# LINE_PREAMP.net
KiCad netlist of a schematic drawn in Altium Designer
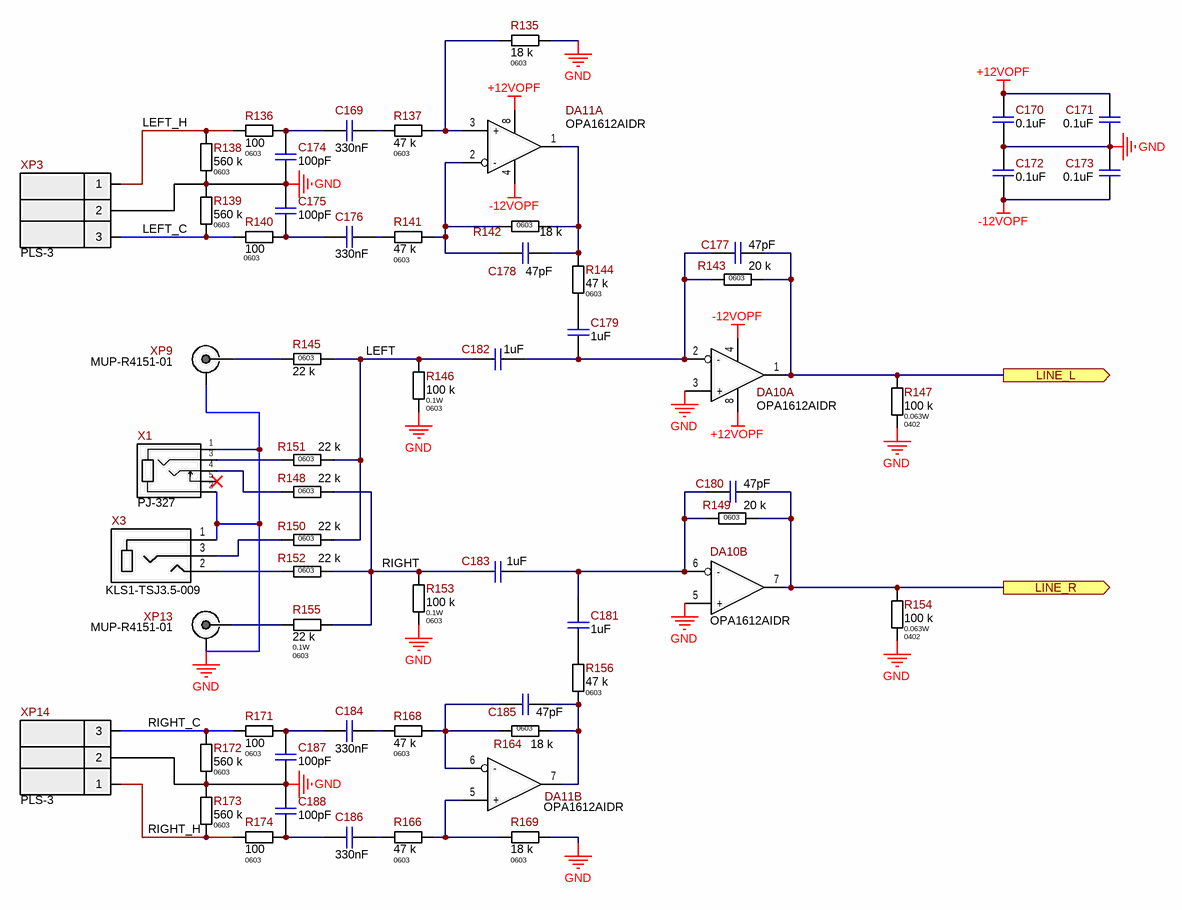
[diagram p0: LINE_PREAMP.SchDoc]

(export (version "E")
  (design (tool "Eeschema 10.0.6"))
  (components
    (comp (ref "C169")
      (value "330nF")
      (footprint "WIMA_2,5x6,5x7,2")
      (description "WIMA 330NF, 40VAC, 63VDC: 5mm, ± 10%")
      (fields (field (name "PART NUMBER") "330nF  AC40V DC63V 2,5x6,5x7,2") (field (name "TOLERANCE") "10%"))
      (libsource (lib "Database") (part "Capacitor_Ceramic"))
    )
    (comp (ref "C170")
      (value "0.1uF")
      (footprint "C0402(1005)")
      (description "CAP CER 0.1UF 25V X7R 0603")
      (fields (field (name "PART NUMBER") "0.1uF  25V C0402") (field (name "TOLERANCE") "±10%"))
      (libsource (lib "Database") (part "Capacitor_Ceramic"))
    )
    (comp (ref "C171")
      (value "0.1uF")
      (footprint "C0402(1005)")
      (description "CAP CER 0.1UF 25V X7R 0603")
      (fields (field (name "PART NUMBER") "0.1uF  25V C0402") (field (name "TOLERANCE") "±10%"))
      (libsource (lib "Database") (part "Capacitor_Ceramic"))
    )
    (comp (ref "C172")
      (value "0.1uF")
      (footprint "C0402(1005)")
      (description "CAP CER 0.1UF 25V X7R 0603")
      (fields (field (name "PART NUMBER") "0.1uF  25V C0402") (field (name "TOLERANCE") "±10%"))
      (libsource (lib "Database") (part "Capacitor_Ceramic"))
    )
    (comp (ref "C173")
      (value "0.1uF")
      (footprint "C0402(1005)")
      (description "CAP CER 0.1UF 25V X7R 0603")
      (fields (field (name "PART NUMBER") "0.1uF  25V C0402") (field (name "TOLERANCE") "±10%"))
      (libsource (lib "Database") (part "Capacitor_Ceramic"))
    )
    (comp (ref "C174")
      (value "100pF")
      (footprint "C0402(1005)")
      (description "CAP CER 100PF 50V NP0 0402")
      (fields (field (name "PART NUMBER") "100pF  50V C0402") (field (name "TOLERANCE") "±0.25pF"))
      (libsource (lib "Database") (part "Capacitor_Ceramic"))
    )
    (comp (ref "C175")
      (value "100pF")
      (footprint "C0402(1005)")
      (description "CAP CER 100PF 50V NP0 0402")
      (fields (field (name "PART NUMBER") "100pF  50V C0402") (field (name "TOLERANCE") "±0.25pF"))
      (libsource (lib "Database") (part "Capacitor_Ceramic"))
    )
    (comp (ref "C176")
      (value "330nF")
      (footprint "WIMA_2,5x6,5x7,2")
      (description "WIMA 330NF, 40VAC, 63VDC: 5mm, ± 10%")
      (fields (field (name "PART NUMBER") "330nF  AC40V DC63V 2,5x6,5x7,2") (field (name "TOLERANCE") "10%"))
      (libsource (lib "Database") (part "Capacitor_Ceramic"))
    )
    (comp (ref "C177")
      (value "47pF")
      (footprint "C0603(1608)")
      (description "CAP CER 47PF 50V X7R 0603")
      (fields (field (name "PART NUMBER") "47pF  50V C0603") (field (name "TOLERANCE") "±10%"))
      (libsource (lib "Database") (part "Capacitor_Ceramic"))
    )
    (comp (ref "C178")
      (value "47pF")
      (footprint "C0603(1608)")
      (description "CAP CER 47PF 50V X7R 0603")
      (fields (field (name "PART NUMBER") "47pF  50V C0603") (field (name "TOLERANCE") "±10%"))
      (libsource (lib "Database") (part "Capacitor_Ceramic"))
    )
    (comp (ref "C179")
      (value "1uF")
      (footprint "WIMA5")
      (description "CAP FILM 1UF 10% 100VDC")
      (fields
        (field (name "PART NUMBER") "1uF  30В AC, 50В DC 5.5x10x7, 2мм")
        (field (name "TOLERANCE") "±10%")
      )
      (libsource (lib "Database") (part "Capacitor_Ceramic"))
    )
    (comp (ref "C180")
      (value "47pF")
      (footprint "C0603(1608)")
      (description "CAP CER 47PF 50V X7R 0603")
      (fields (field (name "PART NUMBER") "47pF  50V C0603") (field (name "TOLERANCE") "±10%"))
      (libsource (lib "Database") (part "Capacitor_Ceramic"))
    )
    (comp (ref "C181")
      (value "1uF")
      (footprint "WIMA5")
      (description "CAP FILM 1UF 10% 100VDC")
      (fields
        (field (name "PART NUMBER") "1uF  30В AC, 50В DC 5.5x10x7, 2мм")
        (field (name "TOLERANCE") "±10%")
      )
      (libsource (lib "Database") (part "Capacitor_Ceramic"))
    )
    (comp (ref "C182")
      (value "1uF")
      (footprint "WIMA5")
      (description "CAP FILM 1UF 10% 100VDC")
      (fields
        (field (name "PART NUMBER") "1uF  30В AC, 50В DC 5.5x10x7, 2мм")
        (field (name "TOLERANCE") "±10%")
      )
      (libsource (lib "Database") (part "Capacitor_Ceramic"))
    )
    (comp (ref "C183")
      (value "1uF")
      (footprint "WIMA5")
      (description "CAP FILM 1UF 10% 100VDC")
      (fields
        (field (name "PART NUMBER") "1uF  30В AC, 50В DC 5.5x10x7, 2мм")
        (field (name "TOLERANCE") "±10%")
      )
      (libsource (lib "Database") (part "Capacitor_Ceramic"))
    )
    (comp (ref "C184")
      (value "330nF")
      (footprint "WIMA_2,5x6,5x7,2")
      (description "WIMA 330NF, 40VAC, 63VDC: 5mm, ± 10%")
      (fields (field (name "PART NUMBER") "330nF  AC40V DC63V 2,5x6,5x7,2") (field (name "TOLERANCE") "10%"))
      (libsource (lib "Database") (part "Capacitor_Ceramic"))
    )
    (comp (ref "C185")
      (value "47pF")
      (footprint "C0603(1608)")
      (description "CAP CER 47PF 50V X7R 0603")
      (fields (field (name "PART NUMBER") "47pF  50V C0603") (field (name "TOLERANCE") "±10%"))
      (libsource (lib "Database") (part "Capacitor_Ceramic"))
    )
    (comp (ref "C186")
      (value "330nF")
      (footprint "WIMA_2,5x6,5x7,2")
      (description "WIMA 330NF, 40VAC, 63VDC: 5mm, ± 10%")
      (fields (field (name "PART NUMBER") "330nF  AC40V DC63V 2,5x6,5x7,2") (field (name "TOLERANCE") "10%"))
      (libsource (lib "Database") (part "Capacitor_Ceramic"))
    )
    (comp (ref "C187")
      (value "100pF")
      (footprint "C0402(1005)")
      (description "CAP CER 100PF 50V NP0 0402")
      (fields (field (name "PART NUMBER") "100pF  50V C0402") (field (name "TOLERANCE") "±0.25pF"))
      (libsource (lib "Database") (part "Capacitor_Ceramic"))
    )
    (comp (ref "C188")
      (value "100pF")
      (footprint "C0402(1005)")
      (description "CAP CER 100PF 50V NP0 0402")
      (fields (field (name "PART NUMBER") "100pF  50V C0402") (field (name "TOLERANCE") "±0.25pF"))
      (libsource (lib "Database") (part "Capacitor_Ceramic"))
    )
    (comp (ref "DA10")
      (value "OPA1612AIDR")
      (footprint "SOIC8")
      (description "Audio Amplifier 2 Circuit Rail-to-Rail 8-SOIC")
      (fields (field (name "MANUFACTURER") "Texas Instruments"))
      (libsource (lib "Database") (part "AMP8"))
    )
    (comp (ref "DA11")
      (value "OPA1612AIDR")
      (footprint "SOIC8")
      (description "Audio Amplifier 2 Circuit Rail-to-Rail 8-SOIC")
      (fields (field (name "MANUFACTURER") "Texas Instruments"))
      (libsource (lib "Database") (part "AMP8"))
    )
    (comp (ref "R135")
      (value "18 k")
      (footprint "R0603")
      (description "RES SMD 18 k OHM  ±1% 1/10W 0603")
      (fields
        (field (name "PACKAGE/CASE") "0603")
        (field (name "PART NUMBER") "18 k  R0603")
        (field (name "TOLERANCE") "±1%")
      )
      (libsource (lib "Database") (part "R0603"))
    )
    (comp (ref "R136")
      (value "100")
      (footprint "R0603")
      (description "RES SMD 100 OHM  ±1% 1/10W 0603")
      (fields
        (field (name "PACKAGE/CASE") "0603")
        (field (name "PART NUMBER") "100  R0603")
        (field (name "TOLERANCE") "±1%")
      )
      (libsource (lib "Database") (part "R0603"))
    )
    (comp (ref "R137")
      (value "47 k")
      (footprint "R0603")
      (description "RES SMD 47 k OHM  ±1% 1/10W 0603")
      (fields
        (field (name "PACKAGE/CASE") "0603")
        (field (name "PART NUMBER") "47 k  R0603")
        (field (name "TOLERANCE") "±1%")
      )
      (libsource (lib "Database") (part "R0603"))
    )
    (comp (ref "R138")
      (value "560 k")
      (footprint "R0603")
      (description "RES SMD 560 k OHM  ±1% 1/10W 0603")
      (fields
        (field (name "PACKAGE/CASE") "0603")
        (field (name "PART NUMBER") "560 k  R0603")
        (field (name "TOLERANCE") "±1%")
      )
      (libsource (lib "Database") (part "R0603"))
    )
    (comp (ref "R139")
      (value "560 k")
      (footprint "R0603")
      (description "RES SMD 560 k OHM  ±1% 1/10W 0603")
      (fields
        (field (name "PACKAGE/CASE") "0603")
        (field (name "PART NUMBER") "560 k  R0603")
        (field (name "TOLERANCE") "±1%")
      )
      (libsource (lib "Database") (part "R0603"))
    )
    (comp (ref "R140")
      (value "100")
      (footprint "R0603")
      (description "RES SMD 100 OHM  ±1% 1/10W 0603")
      (fields
        (field (name "PACKAGE/CASE") "0603")
        (field (name "PART NUMBER") "100  R0603")
        (field (name "TOLERANCE") "±1%")
      )
      (libsource (lib "Database") (part "R0603"))
    )
    (comp (ref "R141")
      (value "47 k")
      (footprint "R0603")
      (description "RES SMD 47 k OHM  ±1% 1/10W 0603")
      (fields
        (field (name "PACKAGE/CASE") "0603")
        (field (name "PART NUMBER") "47 k  R0603")
        (field (name "TOLERANCE") "±1%")
      )
      (libsource (lib "Database") (part "R0603"))
    )
    (comp (ref "R142")
      (value "18 k")
      (footprint "R0603")
      (description "RES SMD 18 k OHM  ±1% 1/10W 0603")
      (fields
        (field (name "PACKAGE/CASE") "0603")
        (field (name "PART NUMBER") "18 k  R0603")
        (field (name "TOLERANCE") "±1%")
      )
      (libsource (lib "Database") (part "R0603"))
    )
    (comp (ref "R143")
      (value "20 k")
      (footprint "R0603")
      (description "RES SMD 20 k OHM  ±1% 1/10W 0603")
      (fields
        (field (name "PACKAGE/CASE") "0603")
        (field (name "PART NUMBER") "20 k  R0603")
        (field (name "TOLERANCE") "±1%")
      )
      (libsource (lib "Database") (part "R0603"))
    )
    (comp (ref "R144")
      (value "47 k")
      (footprint "R0603")
      (description "RES SMD 47 k OHM  ±1% 1/10W 0603")
      (fields
        (field (name "PACKAGE/CASE") "0603")
        (field (name "PART NUMBER") "47 k  R0603")
        (field (name "TOLERANCE") "±1%")
      )
      (libsource (lib "Database") (part "R0603"))
    )
    (comp (ref "R145")
      (value "22 k")
      (footprint "R0603")
      (description "RES SMD 22 k OHM  ±1% 1/10W 0603")
      (fields
        (field (name "PACKAGE/CASE") "0603")
        (field (name "PART NUMBER") "22 k  R0603")
        (field (name "TOLERANCE") "±1%")
      )
      (libsource (lib "Database") (part "R0603"))
    )
    (comp (ref "R146")
      (value "100 k")
      (footprint "R0603")
      (description "RES SMD 100 k OHM  ±1% 1/10W 0603")
      (fields
        (field (name "POWER RATING") "0.1W")
        (field (name "PACKAGE/CASE") "0603")
        (field (name "PART NUMBER") "100 k  R0603")
        (field (name "TOLERANCE") "±1%")
      )
      (libsource (lib "Database") (part "R0603"))
    )
    (comp (ref "R147")
      (value "100 k")
      (footprint "R0402")
      (description "RES SMD 100 k OHM  ±1% 1/16W 0402")
      (fields
        (field (name "POWER RATING") "0.063W")
        (field (name "PACKAGE/CASE") "0402")
        (field (name "PART NUMBER") "100 k  R0402")
        (field (name "TOLERANCE") "±1%")
      )
      (libsource (lib "Database") (part "R0402"))
    )
    (comp (ref "R148")
      (value "22 k")
      (footprint "R0603")
      (description "RES SMD 22 k OHM  ±1% 1/10W 0603")
      (fields
        (field (name "PACKAGE/CASE") "0603")
        (field (name "PART NUMBER") "22 k  R0603")
        (field (name "TOLERANCE") "±1%")
      )
      (libsource (lib "Database") (part "R0603"))
    )
    (comp (ref "R149")
      (value "20 k")
      (footprint "R0603")
      (description "RES SMD 20 k OHM  ±1% 1/10W 0603")
      (fields
        (field (name "PACKAGE/CASE") "0603")
        (field (name "PART NUMBER") "20 k  R0603")
        (field (name "TOLERANCE") "±1%")
      )
      (libsource (lib "Database") (part "R0603"))
    )
    (comp (ref "R150")
      (value "22 k")
      (footprint "R0603")
      (description "RES SMD 22 k OHM  ±1% 1/10W 0603")
      (fields
        (field (name "PACKAGE/CASE") "0603")
        (field (name "PART NUMBER") "22 k  R0603")
        (field (name "TOLERANCE") "±1%")
      )
      (libsource (lib "Database") (part "R0603"))
    )
    (comp (ref "R151")
      (value "22 k")
      (footprint "R0603")
      (description "RES SMD 22 k OHM  ±1% 1/10W 0603")
      (fields
        (field (name "PACKAGE/CASE") "0603")
        (field (name "PART NUMBER") "22 k  R0603")
        (field (name "TOLERANCE") "±1%")
      )
      (libsource (lib "Database") (part "R0603"))
    )
    (comp (ref "R152")
      (value "22 k")
      (footprint "R0603")
      (description "RES SMD 22 k OHM  ±1% 1/10W 0603")
      (fields
        (field (name "PACKAGE/CASE") "0603")
        (field (name "PART NUMBER") "22 k  R0603")
        (field (name "TOLERANCE") "±1%")
      )
      (libsource (lib "Database") (part "R0603"))
    )
    (comp (ref "R153")
      (value "100 k")
      (footprint "R0603")
      (description "RES SMD 100 k OHM  ±1% 1/10W 0603")
      (fields
        (field (name "POWER RATING") "0.1W")
        (field (name "PACKAGE/CASE") "0603")
        (field (name "PART NUMBER") "100 k  R0603")
        (field (name "TOLERANCE") "±1%")
      )
      (libsource (lib "Database") (part "R0603"))
    )
    (comp (ref "R154")
      (value "100 k")
      (footprint "R0402")
      (description "RES SMD 100 k OHM  ±1% 1/16W 0402")
      (fields
        (field (name "POWER RATING") "0.063W")
        (field (name "PACKAGE/CASE") "0402")
        (field (name "PART NUMBER") "100 k  R0402")
        (field (name "TOLERANCE") "±1%")
      )
      (libsource (lib "Database") (part "R0402"))
    )
    (comp (ref "R155")
      (value "22 k")
      (footprint "R0603")
      (description "RES SMD 22 k OHM  ±1% 1/10W 0603")
      (fields
        (field (name "POWER RATING") "0.1W")
        (field (name "PACKAGE/CASE") "0603")
        (field (name "PART NUMBER") "22 k  R0603")
        (field (name "TOLERANCE") "±1%")
      )
      (libsource (lib "Database") (part "R0603"))
    )
    (comp (ref "R156")
      (value "47 k")
      (footprint "R0603")
      (description "RES SMD 47 k OHM  ±1% 1/10W 0603")
      (fields
        (field (name "PACKAGE/CASE") "0603")
        (field (name "PART NUMBER") "47 k  R0603")
        (field (name "TOLERANCE") "±1%")
      )
      (libsource (lib "Database") (part "R0603"))
    )
    (comp (ref "R164")
      (value "18 k")
      (footprint "R0603")
      (description "RES SMD 18 k OHM  ±1% 1/10W 0603")
      (fields
        (field (name "PACKAGE/CASE") "0603")
        (field (name "PART NUMBER") "18 k  R0603")
        (field (name "TOLERANCE") "±1%")
      )
      (libsource (lib "Database") (part "R0603"))
    )
    (comp (ref "R166")
      (value "47 k")
      (footprint "R0603")
      (description "RES SMD 47 k OHM  ±1% 1/10W 0603")
      (fields
        (field (name "PACKAGE/CASE") "0603")
        (field (name "PART NUMBER") "47 k  R0603")
        (field (name "TOLERANCE") "±1%")
      )
      (libsource (lib "Database") (part "R0603"))
    )
    (comp (ref "R168")
      (value "47 k")
      (footprint "R0603")
      (description "RES SMD 47 k OHM  ±1% 1/10W 0603")
      (fields
        (field (name "PACKAGE/CASE") "0603")
        (field (name "PART NUMBER") "47 k  R0603")
        (field (name "TOLERANCE") "±1%")
      )
      (libsource (lib "Database") (part "R0603"))
    )
    (comp (ref "R169")
      (value "18 k")
      (footprint "R0603")
      (description "RES SMD 18 k OHM  ±1% 1/10W 0603")
      (fields
        (field (name "PACKAGE/CASE") "0603")
        (field (name "PART NUMBER") "18 k  R0603")
        (field (name "TOLERANCE") "±1%")
      )
      (libsource (lib "Database") (part "R0603"))
    )
    (comp (ref "R171")
      (value "100")
      (footprint "R0603")
      (description "RES SMD 100 OHM  ±1% 1/10W 0603")
      (fields
        (field (name "PACKAGE/CASE") "0603")
        (field (name "PART NUMBER") "100  R0603")
        (field (name "TOLERANCE") "±1%")
      )
      (libsource (lib "Database") (part "R0603"))
    )
    (comp (ref "R172")
      (value "560 k")
      (footprint "R0603")
      (description "RES SMD 560 k OHM  ±1% 1/10W 0603")
      (fields
        (field (name "PACKAGE/CASE") "0603")
        (field (name "PART NUMBER") "560 k  R0603")
        (field (name "TOLERANCE") "±1%")
      )
      (libsource (lib "Database") (part "R0603"))
    )
    (comp (ref "R173")
      (value "560 k")
      (footprint "R0603")
      (description "RES SMD 560 k OHM  ±1% 1/10W 0603")
      (fields
        (field (name "PACKAGE/CASE") "0603")
        (field (name "PART NUMBER") "560 k  R0603")
        (field (name "TOLERANCE") "±1%")
      )
      (libsource (lib "Database") (part "R0603"))
    )
    (comp (ref "R174")
      (value "100")
      (footprint "R0603")
      (description "RES SMD 100 OHM  ±1% 1/10W 0603")
      (fields
        (field (name "PACKAGE/CASE") "0603")
        (field (name "PART NUMBER") "100  R0603")
        (field (name "TOLERANCE") "±1%")
      )
      (libsource (lib "Database") (part "R0603"))
    )
    (comp (ref "X1")
      (value "PJ-327")
      (footprint "PJ-327A")
      (description "3.5 Audio Jack SMD")
      (fields (field (name "MANUFACTURER_PART_NUMBER") "HFD31/5"))
      (libsource (lib "Database") (part "PJ-327"))
    )
    (comp (ref "X3")
      (value "~")
      (footprint "KLS1-TSJ3.5-009")
      (description "3.5mm DIP Stereo Jack, Right Angle, DC 30V, 0.5A, 2-20N Insertion Force")
      (fields (field (name "MANUFACTURER") "KLS Electronic") (field (name "PART NUMBER") "KLS1-TSJ3.5-009"))
      (libsource (lib "Database") (part "KLS1-TSJ3.5-009"))
    )
    (comp (ref "XP3")
      (value "PLS-3")
      (footprint "3x-2.54")
      (description "CONN HEADER 3POS 2.54MM")
      (fields (field (name "MANUFACTURER") "CONNFLY"))
      (libsource (lib "Database") (part "CON_3"))
    )
    (comp (ref "XP9")
      (value "MUP-R4151-01")
      (footprint "U.FL-R-SMT(10)_REC")
      (description "MHF Series Micro Coaxial Connector Receptacle, Vertical, 3.1x3.0x1.25mm")
      (libsource (lib "Database") (part "IPEX"))
    )
    (comp (ref "XP13")
      (value "MUP-R4151-01")
      (footprint "U.FL-R-SMT(10)_REC")
      (description "MHF Series Micro Coaxial Connector Receptacle, Vertical, 3.1x3.0x1.25mm")
      (libsource (lib "Database") (part "IPEX"))
    )
    (comp (ref "XP14")
      (value "PLS-3")
      (footprint "3x-2.54")
      (description "CONN HEADER 3POS 2.54MM")
      (fields (field (name "MANUFACTURER") "CONNFLY"))
      (libsource (lib "") (part "CON_3_1"))
    )
  )
  (nets
    (net (code "1") (name "+12VOPF") (class "Default")
      (node (ref "C170") (pin "1") (pinfunction "1_1") (pintype "passive"))
      (node (ref "C171") (pin "1") (pinfunction "1_1") (pintype "passive"))
      (node (ref "DA10") (pin "8") (pinfunction "V+_8") (pintype "passive"))
      (node (ref "DA11") (pin "8") (pinfunction "V+_8") (pintype "passive"))
    )
    (net (code "2") (name "-12VOPF") (class "Default")
      (node (ref "C172") (pin "2") (pinfunction "2_2") (pintype "passive"))
      (node (ref "C173") (pin "2") (pinfunction "2_2") (pintype "passive"))
      (node (ref "DA10") (pin "4") (pinfunction "V-_4") (pintype "passive"))
      (node (ref "DA11") (pin "4") (pinfunction "V-_4") (pintype "passive"))
    )
    (net (code "3") (name "/LEFT") (class "Default")
      (node (ref "C182") (pin "1") (pinfunction "1_1") (pintype "passive"))
      (node (ref "R145") (pin "2") (pinfunction "2_2") (pintype "passive"))
      (node (ref "R146") (pin "1") (pinfunction "1_1") (pintype "passive"))
      (node (ref "R150") (pin "2") (pinfunction "2_2") (pintype "passive"))
      (node (ref "R151") (pin "2") (pinfunction "2_2") (pintype "passive"))
    )
    (net (code "4") (name "/LEFT_C") (class "Default")
      (node (ref "R139") (pin "2") (pinfunction "2_2") (pintype "passive"))
      (node (ref "R140") (pin "2") (pinfunction "2_2") (pintype "passive"))
      (node (ref "XP3") (pin "3") (pinfunction "3_3") (pintype "passive"))
    )
    (net (code "5") (name "/LEFT_H") (class "Default")
      (node (ref "R136") (pin "2") (pinfunction "2_2") (pintype "passive"))
      (node (ref "R138") (pin "1") (pinfunction "1_1") (pintype "passive"))
      (node (ref "XP3") (pin "1") (pinfunction "1_1") (pintype "passive"))
    )
    (net (code "6") (name "/LINE_L") (class "Default")
      (node (ref "C177") (pin "1") (pinfunction "1_1") (pintype "passive"))
      (node (ref "DA10") (pin "1") (pinfunction "Out_1") (pintype "passive"))
      (node (ref "R143") (pin "2") (pinfunction "2_2") (pintype "passive"))
      (node (ref "R147") (pin "1") (pinfunction "1_1") (pintype "passive"))
    )
    (net (code "7") (name "/LINE_R") (class "Default")
      (node (ref "C180") (pin "1") (pinfunction "1_1") (pintype "passive"))
      (node (ref "DA10") (pin "7") (pinfunction "Out_7") (pintype "passive"))
      (node (ref "R149") (pin "2") (pinfunction "2_2") (pintype "passive"))
      (node (ref "R154") (pin "1") (pinfunction "1_1") (pintype "passive"))
    )
    (net (code "8") (name "/RIGHT") (class "Default")
      (node (ref "C183") (pin "1") (pinfunction "1_1") (pintype "passive"))
      (node (ref "R148") (pin "2") (pinfunction "2_2") (pintype "passive"))
      (node (ref "R152") (pin "2") (pinfunction "2_2") (pintype "passive"))
      (node (ref "R153") (pin "1") (pinfunction "1_1") (pintype "passive"))
      (node (ref "R155") (pin "2") (pinfunction "2_2") (pintype "passive"))
    )
    (net (code "9") (name "/RIGHT_C") (class "Default")
      (node (ref "R171") (pin "2") (pinfunction "2_2") (pintype "passive"))
      (node (ref "R172") (pin "2") (pinfunction "2_2") (pintype "passive"))
      (node (ref "XP14") (pin "3") (pinfunction "3_3") (pintype "passive"))
    )
    (net (code "10") (name "/RIGHT_H") (class "Default")
      (node (ref "R173") (pin "1") (pinfunction "1_1") (pintype "passive"))
      (node (ref "R174") (pin "2") (pinfunction "2_2") (pintype "passive"))
      (node (ref "XP14") (pin "1") (pinfunction "1_1") (pintype "passive"))
    )
    (net (code "11") (name "GND") (class "Default")
      (node (ref "C170") (pin "2") (pinfunction "2_2") (pintype "passive"))
      (node (ref "C171") (pin "2") (pinfunction "2_2") (pintype "passive"))
      (node (ref "C172") (pin "1") (pinfunction "1_1") (pintype "passive"))
      (node (ref "C173") (pin "1") (pinfunction "1_1") (pintype "passive"))
      (node (ref "C174") (pin "2") (pinfunction "2_2") (pintype "passive"))
      (node (ref "C175") (pin "2") (pinfunction "2_2") (pintype "passive"))
      (node (ref "C187") (pin "2") (pinfunction "2_2") (pintype "passive"))
      (node (ref "C188") (pin "2") (pinfunction "2_2") (pintype "passive"))
      (node (ref "DA10") (pin "3") (pinfunction "+_3") (pintype "passive"))
      (node (ref "DA10") (pin "5") (pinfunction "+_5") (pintype "passive"))
      (node (ref "R135") (pin "1") (pinfunction "1_1") (pintype "passive"))
      (node (ref "R138") (pin "2") (pinfunction "2_2") (pintype "passive"))
      (node (ref "R139") (pin "1") (pinfunction "1_1") (pintype "passive"))
      (node (ref "R146") (pin "2") (pinfunction "2_2") (pintype "passive"))
      (node (ref "R147") (pin "2") (pinfunction "2_2") (pintype "passive"))
      (node (ref "R153") (pin "2") (pinfunction "2_2") (pintype "passive"))
      (node (ref "R154") (pin "2") (pinfunction "2_2") (pintype "passive"))
      (node (ref "R169") (pin "1") (pinfunction "1_1") (pintype "passive"))
      (node (ref "R172") (pin "1") (pinfunction "1_1") (pintype "passive"))
      (node (ref "R173") (pin "2") (pinfunction "2_2") (pintype "passive"))
      (node (ref "X1") (pin "1") (pinfunction "GND_1") (pintype "passive"))
      (node (ref "X1") (pin "2") (pinfunction "GND_2") (pintype "passive"))
      (node (ref "X3") (pin "1") (pinfunction "1_1") (pintype "passive"))
      (node (ref "XP13") (pin "2") (pinfunction "2_2") (pintype "passive"))
      (node (ref "XP14") (pin "2") (pinfunction "2_2") (pintype "passive"))
      (node (ref "XP3") (pin "2") (pinfunction "2_2") (pintype "passive"))
      (node (ref "XP9") (pin "2") (pinfunction "2_2") (pintype "passive"))
    )
    (net (code "12") (name "Net-(C169-Pad1)") (class "Default")
      (node (ref "C169") (pin "1") (pinfunction "1_1") (pintype "passive"))
      (node (ref "C174") (pin "1") (pinfunction "1_1") (pintype "passive"))
      (node (ref "R136") (pin "1") (pinfunction "1_1") (pintype "passive"))
    )
    (net (code "13") (name "Net-(C169-Pad2)") (class "Default")
      (node (ref "C169") (pin "2") (pinfunction "2_2") (pintype "passive"))
      (node (ref "R137") (pin "1") (pinfunction "1_1") (pintype "passive"))
    )
    (net (code "14") (name "Net-(C175-Pad1)") (class "Default")
      (node (ref "C175") (pin "1") (pinfunction "1_1") (pintype "passive"))
      (node (ref "C176") (pin "1") (pinfunction "1_1") (pintype "passive"))
      (node (ref "R140") (pin "1") (pinfunction "1_1") (pintype "passive"))
    )
    (net (code "15") (name "Net-(C176-Pad2)") (class "Default")
      (node (ref "C176") (pin "2") (pinfunction "2_2") (pintype "passive"))
      (node (ref "R141") (pin "2") (pinfunction "2_2") (pintype "passive"))
    )
    (net (code "16") (name "Net-(C179-Pad1)") (class "Default")
      (node (ref "C179") (pin "1") (pinfunction "1_1") (pintype "passive"))
      (node (ref "R144") (pin "1") (pinfunction "1_1") (pintype "passive"))
    )
    (net (code "17") (name "Net-(C181-Pad1)") (class "Default")
      (node (ref "C181") (pin "1") (pinfunction "1_1") (pintype "passive"))
      (node (ref "R156") (pin "1") (pinfunction "1_1") (pintype "passive"))
    )
    (net (code "18") (name "Net-(C184-Pad1)") (class "Default")
      (node (ref "C184") (pin "1") (pinfunction "1_1") (pintype "passive"))
      (node (ref "C187") (pin "1") (pinfunction "1_1") (pintype "passive"))
      (node (ref "R171") (pin "1") (pinfunction "1_1") (pintype "passive"))
    )
    (net (code "19") (name "Net-(C184-Pad2)") (class "Default")
      (node (ref "C184") (pin "2") (pinfunction "2_2") (pintype "passive"))
      (node (ref "R168") (pin "2") (pinfunction "2_2") (pintype "passive"))
    )
    (net (code "20") (name "Net-(C186-Pad1)") (class "Default")
      (node (ref "C186") (pin "1") (pinfunction "1_1") (pintype "passive"))
      (node (ref "C188") (pin "1") (pinfunction "1_1") (pintype "passive"))
      (node (ref "R174") (pin "1") (pinfunction "1_1") (pintype "passive"))
    )
    (net (code "21") (name "Net-(C186-Pad2)") (class "Default")
      (node (ref "C186") (pin "2") (pinfunction "2_2") (pintype "passive"))
      (node (ref "R166") (pin "1") (pinfunction "1_1") (pintype "passive"))
    )
    (net (code "22") (name "Net-(DA10A--)") (class "Default")
      (node (ref "C177") (pin "2") (pinfunction "2_2") (pintype "passive"))
      (node (ref "C179") (pin "2") (pinfunction "2_2") (pintype "passive"))
      (node (ref "C182") (pin "2") (pinfunction "2_2") (pintype "passive"))
      (node (ref "DA10") (pin "2") (pinfunction "-_2") (pintype "passive"))
      (node (ref "R143") (pin "1") (pinfunction "1_1") (pintype "passive"))
    )
    (net (code "23") (name "Net-(DA10B--)") (class "Default")
      (node (ref "C180") (pin "2") (pinfunction "2_2") (pintype "passive"))
      (node (ref "C181") (pin "2") (pinfunction "2_2") (pintype "passive"))
      (node (ref "C183") (pin "2") (pinfunction "2_2") (pintype "passive"))
      (node (ref "DA10") (pin "6") (pinfunction "-_6") (pintype "passive"))
      (node (ref "R149") (pin "1") (pinfunction "1_1") (pintype "passive"))
    )
    (net (code "24") (name "Net-(DA11A-+)") (class "Default")
      (node (ref "DA11") (pin "3") (pinfunction "+_3") (pintype "passive"))
      (node (ref "R135") (pin "2") (pinfunction "2_2") (pintype "passive"))
      (node (ref "R137") (pin "2") (pinfunction "2_2") (pintype "passive"))
    )
    (net (code "25") (name "Net-(DA11A--)") (class "Default")
      (node (ref "C178") (pin "2") (pinfunction "2_2") (pintype "passive"))
      (node (ref "DA11") (pin "2") (pinfunction "-_2") (pintype "passive"))
      (node (ref "R141") (pin "1") (pinfunction "1_1") (pintype "passive"))
      (node (ref "R142") (pin "2") (pinfunction "2_2") (pintype "passive"))
    )
    (net (code "26") (name "Net-(DA11A-Out)") (class "Default")
      (node (ref "C178") (pin "1") (pinfunction "1_1") (pintype "passive"))
      (node (ref "DA11") (pin "1") (pinfunction "Out_1") (pintype "passive"))
      (node (ref "R142") (pin "1") (pinfunction "1_1") (pintype "passive"))
      (node (ref "R144") (pin "2") (pinfunction "2_2") (pintype "passive"))
    )
    (net (code "27") (name "Net-(DA11B-+)") (class "Default")
      (node (ref "DA11") (pin "5") (pinfunction "+_5") (pintype "passive"))
      (node (ref "R166") (pin "2") (pinfunction "2_2") (pintype "passive"))
      (node (ref "R169") (pin "2") (pinfunction "2_2") (pintype "passive"))
    )
    (net (code "28") (name "Net-(DA11B--)") (class "Default")
      (node (ref "C185") (pin "2") (pinfunction "2_2") (pintype "passive"))
      (node (ref "DA11") (pin "6") (pinfunction "-_6") (pintype "passive"))
      (node (ref "R164") (pin "2") (pinfunction "2_2") (pintype "passive"))
      (node (ref "R168") (pin "1") (pinfunction "1_1") (pintype "passive"))
    )
    (net (code "29") (name "Net-(DA11B-Out)") (class "Default")
      (node (ref "C185") (pin "1") (pinfunction "1_1") (pintype "passive"))
      (node (ref "DA11") (pin "7") (pinfunction "Out_7") (pintype "passive"))
      (node (ref "R156") (pin "2") (pinfunction "2_2") (pintype "passive"))
      (node (ref "R164") (pin "1") (pinfunction "1_1") (pintype "passive"))
    )
    (net (code "30") (name "Net-(R145-Pad1)") (class "Default")
      (node (ref "R145") (pin "1") (pinfunction "1_1") (pintype "passive"))
      (node (ref "XP9") (pin "1") (pinfunction "1_1") (pintype "passive"))
    )
    (net (code "31") (name "Net-(R148-Pad1)") (class "Default")
      (node (ref "R148") (pin "1") (pinfunction "1_1") (pintype "passive"))
      (node (ref "X1") (pin "4") (pinfunction "GND_4") (pintype "passive"))
    )
    (net (code "32") (name "Net-(R150-Pad1)") (class "Default")
      (node (ref "R150") (pin "1") (pinfunction "1_1") (pintype "passive"))
      (node (ref "X3") (pin "3") (pinfunction "3_3") (pintype "passive"))
    )
    (net (code "33") (name "Net-(R151-Pad1)") (class "Default")
      (node (ref "R151") (pin "1") (pinfunction "1_1") (pintype "passive"))
      (node (ref "X1") (pin "3") (pinfunction "GND_3") (pintype "passive"))
    )
    (net (code "34") (name "Net-(R152-Pad1)") (class "Default")
      (node (ref "R152") (pin "1") (pinfunction "1_1") (pintype "passive"))
      (node (ref "X3") (pin "2") (pinfunction "2_2") (pintype "passive"))
    )
    (net (code "35") (name "Net-(R155-Pad1)") (class "Default")
      (node (ref "R155") (pin "1") (pinfunction "1_1") (pintype "passive"))
      (node (ref "XP13") (pin "1") (pinfunction "1_1") (pintype "passive"))
    )
    (net (code "36") (name "unconnected-(X1-GND-Pad5)") (class "Default")
      (node (ref "X1") (pin "5") (pinfunction "GND_5") (pintype "passive+no_connect"))
    )
  )
)
